# yard-ice-cpu.net
KiCad netlist of a schematic drawn in Altium Designer
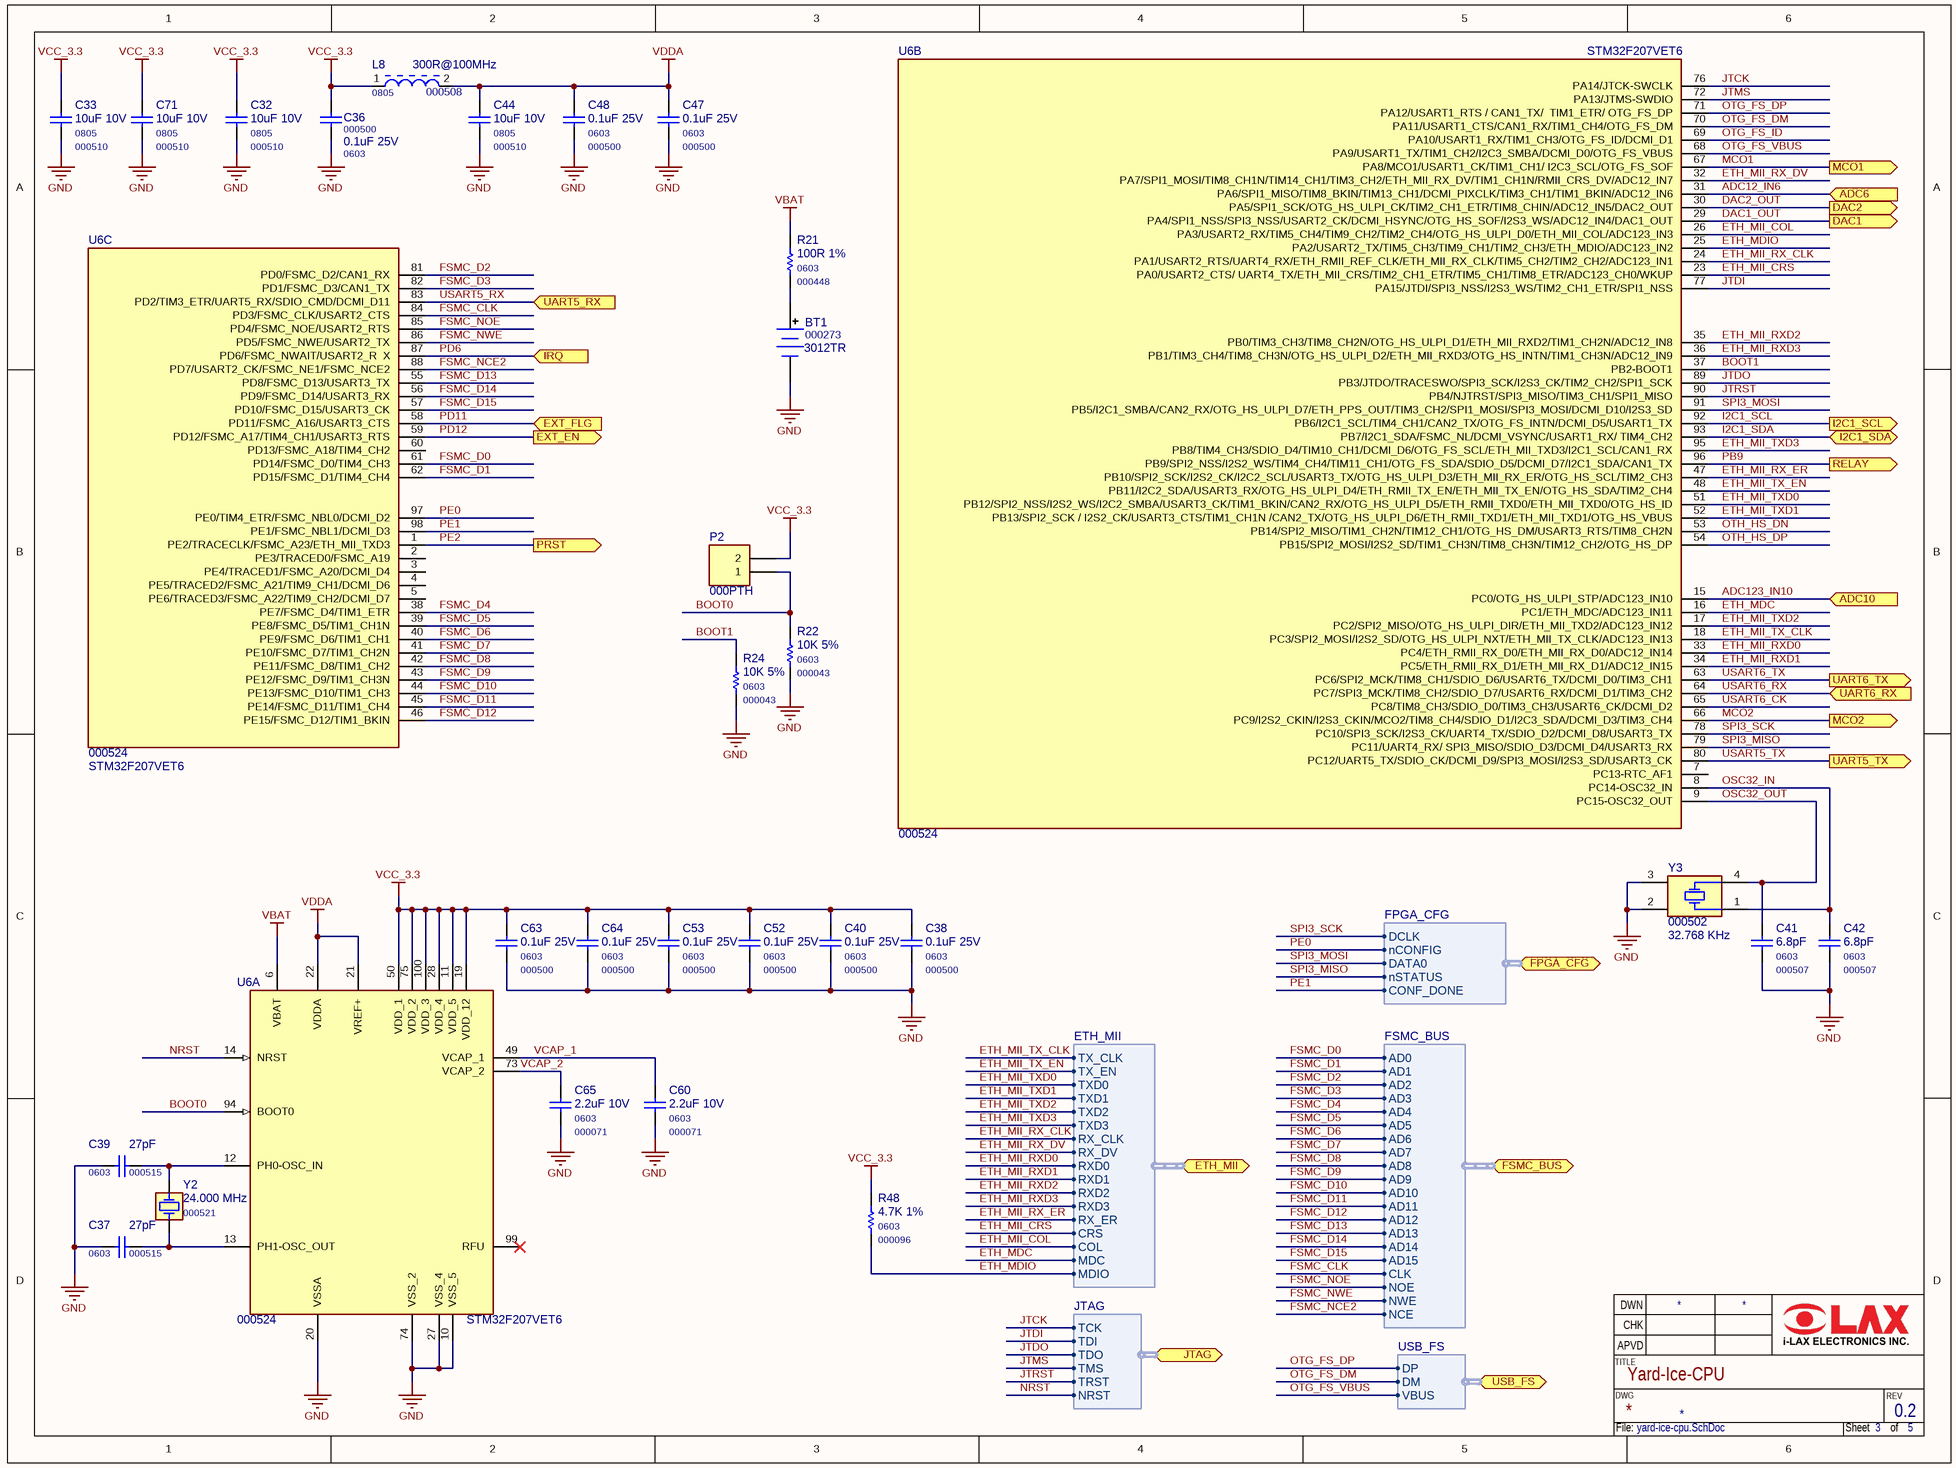
[diagram p0: yard-ice-cpu.SchDoc]

(export (version "E")
  (design (tool "Eeschema 10.0.6"))
  (components
    (comp (ref "BT1")
      (value "000273")
      (footprint "3012TR")
      (description "CR1620 SMD Battery Holder")
      (fields (field (name "MF") "Kestone") (field (name "ALTIUM_VALUE") "3012TR"))
      (libsource (lib "discrete-sm") (part "3012TR"))
    )
    (comp (ref "C32")
      (value "TDK")
      (footprint "C0805M")
      (description "SMD Ceramic Chip Capacitor - 0805 - X7R")
      (fields (field (name "ALTIUM_VALUE") "10uF 10V") (field (name "PACKAGE") "0805"))
      (libsource (lib "discrete-sm") (part "C0805"))
    )
    (comp (ref "C33")
      (value "TDK")
      (footprint "C0805M")
      (description "SMD Ceramic Chip Capacitor - 0805 - X7R")
      (fields (field (name "ALTIUM_VALUE") "10uF 10V") (field (name "PACKAGE") "0805"))
      (libsource (lib "discrete-sm") (part "C0805"))
    )
    (comp (ref "C36")
      (value "000500")
      (footprint "C0603M")
      (description "SMD Ceramic Chip Capacitor - 0603 - X7R")
      (fields
        (field (name "ALTIUM_VALUE") "0.1uF 25V")
        (field (name "PACKAGE") "0603")
        (field (name "MF") "TDK")
      )
      (libsource (lib "discrete-sm") (part "C0603"))
    )
    (comp (ref "C37")
      (value "000515")
      (footprint "C0603M")
      (description "SMD Ceramic Chip Capacitor - 0603")
      (fields (field (name "ALTIUM_VALUE") "27pF") (field (name "PACKAGE") "0603"))
      (libsource (lib "discrete-sm") (part "C0603"))
    )
    (comp (ref "C38")
      (value "000500")
      (footprint "C0603M")
      (description "SMD Ceramic Chip Capacitor - 0603 - X7R")
      (fields
        (field (name "ALTIUM_VALUE") "0.1uF 25V")
        (field (name "PACKAGE") "0603")
        (field (name "MF") "TDK")
      )
      (libsource (lib "discrete-sm") (part "C0603"))
    )
    (comp (ref "C39")
      (value "000515")
      (footprint "C0603M")
      (description "SMD Ceramic Chip Capacitor - 0603")
      (fields (field (name "ALTIUM_VALUE") "27pF") (field (name "PACKAGE") "0603"))
      (libsource (lib "discrete-sm") (part "C0603"))
    )
    (comp (ref "C40")
      (value "000500")
      (footprint "C0603M")
      (description "SMD Ceramic Chip Capacitor - 0603 - X7R")
      (fields
        (field (name "ALTIUM_VALUE") "0.1uF 25V")
        (field (name "PACKAGE") "0603")
        (field (name "MF") "TDK")
      )
      (libsource (lib "discrete-sm") (part "C0603"))
    )
    (comp (ref "C41")
      (value "000507")
      (footprint "C0603M")
      (description "SMD Ceramic Chip Capacitor - 0603")
      (fields (field (name "ALTIUM_VALUE") "6.8pF") (field (name "PACKAGE") "0603"))
      (libsource (lib "discrete-sm") (part "C0603"))
    )
    (comp (ref "C42")
      (value "000507")
      (footprint "C0603M")
      (description "SMD Ceramic Chip Capacitor - 0603")
      (fields (field (name "ALTIUM_VALUE") "6.8pF") (field (name "PACKAGE") "0603"))
      (libsource (lib "discrete-sm") (part "C0603"))
    )
    (comp (ref "C44")
      (value "000510")
      (footprint "C0805M")
      (description "SMD Ceramic Chip Capacitor - 0805 - X7R")
      (fields
        (field (name "ALTIUM_VALUE") "10uF 10V")
        (field (name "PACKAGE") "0805")
        (field (name "MF") "TDK")
      )
      (libsource (lib "discrete-sm") (part "C0805"))
    )
    (comp (ref "C47")
      (value "000500")
      (footprint "C0603M")
      (description "SMD Ceramic Chip Capacitor - 0603 - X7R")
      (fields
        (field (name "ALTIUM_VALUE") "0.1uF 25V")
        (field (name "PACKAGE") "0603")
        (field (name "MF") "TDK")
      )
      (libsource (lib "discrete-sm") (part "C0603"))
    )
    (comp (ref "C48")
      (value "000500")
      (footprint "C0603M")
      (description "SMD Ceramic Chip Capacitor - 0603 - X7R")
      (fields
        (field (name "ALTIUM_VALUE") "0.1uF 25V")
        (field (name "PACKAGE") "0603")
        (field (name "MF") "TDK")
      )
      (libsource (lib "discrete-sm") (part "C0603"))
    )
    (comp (ref "C52")
      (value "000500")
      (footprint "C0603M")
      (description "SMD Ceramic Chip Capacitor - 0603 - X7R")
      (fields
        (field (name "ALTIUM_VALUE") "0.1uF 25V")
        (field (name "PACKAGE") "0603")
        (field (name "MF") "TDK")
      )
      (libsource (lib "discrete-sm") (part "C0603"))
    )
    (comp (ref "C53")
      (value "000500")
      (footprint "C0603M")
      (description "SMD Ceramic Chip Capacitor - 0603 - X7R")
      (fields
        (field (name "ALTIUM_VALUE") "0.1uF 25V")
        (field (name "PACKAGE") "0603")
        (field (name "MF") "TDK")
      )
      (libsource (lib "discrete-sm") (part "C0603"))
    )
    (comp (ref "C60")
      (value "000071")
      (footprint "C0603M")
      (description "SMD Ceramic Chip Capacitor - 0603 - X7R")
      (fields
        (field (name "ALTIUM_VALUE") "2.2uF 10V")
        (field (name "PACKAGE") "0603")
        (field (name "MF") "Taiyo Yuden")
      )
      (libsource (lib "discrete-sm") (part "C0603"))
    )
    (comp (ref "C63")
      (value "000500")
      (footprint "C0603M")
      (description "SMD Ceramic Chip Capacitor - 0603 - X7R")
      (fields
        (field (name "ALTIUM_VALUE") "0.1uF 25V")
        (field (name "PACKAGE") "0603")
        (field (name "MF") "TDK")
      )
      (libsource (lib "discrete-sm") (part "C0603"))
    )
    (comp (ref "C64")
      (value "000500")
      (footprint "C0603M")
      (description "SMD Ceramic Chip Capacitor - 0603 - X7R")
      (fields
        (field (name "ALTIUM_VALUE") "0.1uF 25V")
        (field (name "PACKAGE") "0603")
        (field (name "MF") "TDK")
      )
      (libsource (lib "discrete-sm") (part "C0603"))
    )
    (comp (ref "C65")
      (value "000071")
      (footprint "C0603M")
      (description "SMD Ceramic Chip Capacitor - 0603 - X7R")
      (fields
        (field (name "ALTIUM_VALUE") "2.2uF 10V")
        (field (name "PACKAGE") "0603")
        (field (name "MF") "Taiyo Yuden")
      )
      (libsource (lib "discrete-sm") (part "C0603"))
    )
    (comp (ref "C71")
      (value "TDK")
      (footprint "C0805M")
      (description "SMD Ceramic Chip Capacitor - 0805 - X7R")
      (fields (field (name "ALTIUM_VALUE") "10uF 10V") (field (name "PACKAGE") "0805"))
      (libsource (lib "discrete-sm") (part "C0805"))
    )
    (comp (ref "L8")
      (value "000508")
      (footprint "L0805M")
      (description "SMD Ferrite Bead 0805")
      (fields
        (field (name "ALTIUM_VALUE") "300R@100MHz")
        (field (name "PACKAGE") "0805")
        (field (name "MF") "TDK")
      )
      (libsource (lib "discrete-sm") (part "L0805"))
    )
    (comp (ref "P2")
      (value "000PTH")
      (footprint "TSW-102-07-G-S")
      (description "Header, 2-Pin")
      (libsource (lib "samtec-board-to-board") (part "Header 2"))
    )
    (comp (ref "R21")
      (value "000448")
      (footprint "R0603M")
      (description "SMD Chip Resistor - 0603")
      (fields (field (name "ALTIUM_VALUE") "100R 1%") (field (name "PACKAGE") "0603"))
      (libsource (lib "discrete-sm") (part "R0603"))
    )
    (comp (ref "R22")
      (value "000043")
      (footprint "R0603M")
      (description "SMD Chip Resistor - 0603")
      (fields (field (name "ALTIUM_VALUE") "10K 5%") (field (name "PACKAGE") "0603"))
      (libsource (lib "discrete-sm") (part "R0603"))
    )
    (comp (ref "R24")
      (value "000043")
      (footprint "R0603M")
      (description "SMD Chip Resistor - 0603")
      (fields (field (name "ALTIUM_VALUE") "10K 5%") (field (name "PACKAGE") "0603"))
      (libsource (lib "discrete-sm") (part "R0603"))
    )
    (comp (ref "R48")
      (value "000096")
      (footprint "R0603M")
      (description "SMD Chip Resistor - 0603")
      (fields (field (name "ALTIUM_VALUE") "4.7K 1%") (field (name "PACKAGE") "0603"))
      (libsource (lib "discrete-sm") (part "R0603"))
    )
    (comp (ref "U6")
      (value "000524")
      (footprint "LQFP100")
      (description "ARM-Cortex M3 MCU, 512KB Flash/128+4KB RAM, USB, Eth")
      (fields (field (name "ALTIUM_VALUE") "STM32F207VET6") (field (name "MF") "ST"))
      (libsource (lib "st-mpu") (part "STM32F207VET6"))
    )
    (comp (ref "Y2")
      (value "000521")
      (footprint "ABM3-H")
      (description "Miniature Ceramic SMD Crystal")
      (fields (field (name "MF") "Abracon") (field (name "ALTIUM_VALUE") "24.000 MHz"))
      (libsource (lib "abracon") (part "ABM3"))
    )
    (comp (ref "Y3")
      (value "000502")
      (footprint "ABS25")
      (description "SMD Low Frequency Crystal")
      (fields (field (name "ALTIUM_VALUE") "32.768 KHz") (field (name "MF") "Abracon"))
      (libsource (lib "abracon") (part "ABS25"))
    )
  )
  (nets
    (net (code "6") (name "/ADC12_IN6") (class "Default")
      (node (ref "U6") (pin "31") (pinfunction "PA6/SPI1_MISO/TIM8_BKIN/TIM13_CH1/DCMI_PIXCLK/TIM3_CH1/TIM1_BKIN/ADC12_IN6_31") (pintype "tri_state"))
    )
    (net (code "7") (name "/ADC123_IN10") (class "Default")
      (node (ref "U6") (pin "15") (pinfunction "PC0/OTG_HS_ULPI_STP/ADC123_IN10_15") (pintype "tri_state"))
    )
    (net (code "8") (name "/BOOT0") (class "Default")
      (node (ref "P2") (pin "1") (pinfunction "1_1") (pintype "passive"))
      (node (ref "R22") (pin "2") (pinfunction "2_2") (pintype "passive"))
      (node (ref "U6") (pin "94") (pinfunction "BOOT0_94") (pintype "input"))
    )
    (net (code "9") (name "/BOOT1") (class "Default")
      (node (ref "R24") (pin "2") (pinfunction "2_2") (pintype "passive"))
      (node (ref "U6") (pin "37") (pinfunction "PB2-BOOT1_37") (pintype "tri_state"))
    )
    (net (code "10") (name "/DAC1_OUT") (class "Default")
      (node (ref "U6") (pin "29") (pinfunction "PA4/SPI1_NSS/SPI3_NSS/USART2_CK/DCMI_HSYNC/OTG_HS_SOF/I2S3_WS/ADC12_IN4/DAC1_OUT_29") (pintype "tri_state"))
    )
    (net (code "11") (name "/DAC2_OUT") (class "Default")
      (node (ref "U6") (pin "30") (pinfunction "PA5/SPI1_SCK/OTG_HS_ULPI_CK/TIM2_CH1_ETR/TIM8_CHIN/ADC12_IN5/DAC2_OUT_30") (pintype "tri_state"))
    )
    (net (code "12") (name "/ETH_MDC") (class "Default")
      (node (ref "U6") (pin "16") (pinfunction "PC1/ETH_MDC/ADC123_IN11_16") (pintype "tri_state"))
    )
    (net (code "13") (name "/ETH_MDIO") (class "Default")
      (node (ref "R48") (pin "1") (pinfunction "1_1") (pintype "passive"))
      (node (ref "U6") (pin "25") (pinfunction "PA2/USART2_TX/TIM5_CH3/TIM9_CH1/TIM2_CH3/ETH_MDIO/ADC123_IN2_25") (pintype "tri_state"))
    )
    (net (code "14") (name "/ETH_MII_COL") (class "Default")
      (node (ref "U6") (pin "26") (pinfunction "PA3/USART2_RX/TIM5_CH4/TIM9_CH2/TIM2_CH4/OTG_HS_ULPI_D0/ETH_MII_COL/ADC123_IN3_26") (pintype "tri_state"))
    )
    (net (code "15") (name "/ETH_MII_CRS") (class "Default")
      (node (ref "U6") (pin "23") (pinfunction "PA0/USART2_CTS/_UART4_TX/ETH_MII_CRS/TIM2_CH1_ETR/TIM5_CH1/TIM8_ETR/ADC123_CH0/WKUP_23") (pintype "tri_state"))
    )
    (net (code "16") (name "/ETH_MII_RXD0") (class "Default")
      (node (ref "U6") (pin "33") (pinfunction "PC4/ETH_RMII_RX_D0/ETH_MII_RX_D0/ADC12_IN14_33") (pintype "tri_state"))
    )
    (net (code "17") (name "/ETH_MII_RXD1") (class "Default")
      (node (ref "U6") (pin "34") (pinfunction "PC5/ETH_RMII_RX_D1/ETH_MII_RX_D1/ADC12_IN15_34") (pintype "tri_state"))
    )
    (net (code "18") (name "/ETH_MII_RXD2") (class "Default")
      (node (ref "U6") (pin "35") (pinfunction "PB0/TIM3_CH3/TIM8_CH2N/OTG_HS_ULPI_D1/ETH_MII_RXD2/TIM1_CH2N/ADC12_IN8_35") (pintype "tri_state"))
    )
    (net (code "19") (name "/ETH_MII_RXD3") (class "Default")
      (node (ref "U6") (pin "36") (pinfunction "PB1/TIM3_CH4/TIM8_CH3N/OTG_HS_ULPI_D2/ETH_MII_RXD3/OTG_HS_INTN/TIM1_CH3N/ADC12_IN9_36") (pintype "tri_state"))
    )
    (net (code "20") (name "/ETH_MII_RX_CLK") (class "Default")
      (node (ref "U6") (pin "24") (pinfunction "PA1/USART2_RTS/UART4_RX/ETH_RMII_REF_CLK/ETH_MII_RX_CLK/TIM5_CH2/TIM2_CH2/ADC123_IN1_24") (pintype "tri_state"))
    )
    (net (code "21") (name "/ETH_MII_RX_DV") (class "Default")
      (node (ref "U6") (pin "32") (pinfunction "PA7/SPI1_MOSI/TIM8_CH1N/TIM14_CH1/TIM3_CH2/ETH_MII_RX_DV/TIM1_CH1N/RMII_CRS_DV/ADC12_IN7_32") (pintype "tri_state"))
    )
    (net (code "22") (name "/ETH_MII_RX_ER") (class "Default")
      (node (ref "U6") (pin "47") (pinfunction "PB10/SPI2_SCK/I2S2_CK/I2C2_SCL/USART3_TX/OTG_HS_ULPI_D3/ETH_MII_RX_ER/OTG_HS_SCL/TIM2_CH3_47") (pintype "tri_state"))
    )
    (net (code "23") (name "/ETH_MII_TXD0") (class "Default")
      (node (ref "U6") (pin "51") (pinfunction "PB12/SPI2_NSS/I2S2_WS/I2C2_SMBA/USART3_CK/TIM1_BKIN/CAN2_RX/OTG_HS_ULPI_D5/ETH_RMII_TXD0/ETH_MII_TXD0/OTG_HS_ID_51") (pintype "tri_state"))
    )
    (net (code "24") (name "/ETH_MII_TXD1") (class "Default")
      (node (ref "U6") (pin "52") (pinfunction "PB13/SPI2_SCK_/_I2S2_CK/USART3_CTS/TIM1_CH1N_/CAN2_TX/OTG_HS_ULPI_D6/ETH_RMII_TXD1/ETH_MII_TXD1/OTG_HS_VBUS_52") (pintype "tri_state"))
    )
    (net (code "25") (name "/ETH_MII_TXD2") (class "Default")
      (node (ref "U6") (pin "17") (pinfunction "PC2/SPI2_MISO/OTG_HS_ULPI_DIR/ETH_MII_TXD2/ADC123_IN12_17") (pintype "tri_state"))
    )
    (net (code "26") (name "/ETH_MII_TXD3") (class "Default")
      (node (ref "U6") (pin "95") (pinfunction "PB8/TIM4_CH3/SDIO_D4/TIM10_CH1/DCMI_D6/OTG_FS_SCL/ETH_MII_TXD3/I2C1_SCL/CAN1_RX_95") (pintype "tri_state"))
    )
    (net (code "27") (name "/ETH_MII_TX_CLK") (class "Default")
      (node (ref "U6") (pin "18") (pinfunction "PC3/SPI2_MOSI/I2S2_SD/OTG_HS_ULPI_NXT/ETH_MII_TX_CLK/ADC123_IN13_18") (pintype "tri_state"))
    )
    (net (code "28") (name "/ETH_MII_TX_EN") (class "Default")
      (node (ref "U6") (pin "48") (pinfunction "PB11/I2C2_SDA/USART3_RX/OTG_HS_ULPI_D4/ETH_RMII_TX_EN/ETH_MII_TX_EN/OTG_HS_SDA/TIM2_CH4_48") (pintype "tri_state"))
    )
    (net (code "29") (name "/FSMC_CLK") (class "Default")
      (node (ref "U6") (pin "84") (pinfunction "PD3/FSMC_CLK/USART2_CTS_84") (pintype "tri_state"))
    )
    (net (code "30") (name "/FSMC_D0") (class "Default")
      (node (ref "U6") (pin "61") (pinfunction "PD14/FSMC_D0/TIM4_CH3_61") (pintype "tri_state"))
    )
    (net (code "31") (name "/FSMC_D1") (class "Default")
      (node (ref "U6") (pin "62") (pinfunction "PD15/FSMC_D1/TIM4_CH4_62") (pintype "tri_state"))
    )
    (net (code "32") (name "/FSMC_D2") (class "Default")
      (node (ref "U6") (pin "81") (pinfunction "PD0/FSMC_D2/CAN1_RX_81") (pintype "tri_state"))
    )
    (net (code "33") (name "/FSMC_D3") (class "Default")
      (node (ref "U6") (pin "82") (pinfunction "PD1/FSMC_D3/CAN1_TX_82") (pintype "tri_state"))
    )
    (net (code "34") (name "/FSMC_D4") (class "Default")
      (node (ref "U6") (pin "38") (pinfunction "PE7/FSMC_D4/TIM1_ETR_38") (pintype "tri_state"))
    )
    (net (code "35") (name "/FSMC_D5") (class "Default")
      (node (ref "U6") (pin "39") (pinfunction "PE8/FSMC_D5/TIM1_CH1N_39") (pintype "tri_state"))
    )
    (net (code "36") (name "/FSMC_D6") (class "Default")
      (node (ref "U6") (pin "40") (pinfunction "PE9/FSMC_D6/TIM1_CH1_40") (pintype "tri_state"))
    )
    (net (code "37") (name "/FSMC_D7") (class "Default")
      (node (ref "U6") (pin "41") (pinfunction "PE10/FSMC_D7/TIM1_CH2N_41") (pintype "tri_state"))
    )
    (net (code "38") (name "/FSMC_D8") (class "Default")
      (node (ref "U6") (pin "42") (pinfunction "PE11/FSMC_D8/TIM1_CH2_42") (pintype "tri_state"))
    )
    (net (code "39") (name "/FSMC_D9") (class "Default")
      (node (ref "U6") (pin "43") (pinfunction "PE12/FSMC_D9/TIM1_CH3N_43") (pintype "tri_state"))
    )
    (net (code "40") (name "/FSMC_D10") (class "Default")
      (node (ref "U6") (pin "44") (pinfunction "PE13/FSMC_D10/TIM1_CH3_44") (pintype "tri_state"))
    )
    (net (code "41") (name "/FSMC_D11") (class "Default")
      (node (ref "U6") (pin "45") (pinfunction "PE14/FSMC_D11/TIM1_CH4_45") (pintype "tri_state"))
    )
    (net (code "42") (name "/FSMC_D12") (class "Default")
      (node (ref "U6") (pin "46") (pinfunction "PE15/FSMC_D12/TIM1_BKIN_46") (pintype "tri_state"))
    )
    (net (code "43") (name "/FSMC_D13") (class "Default")
      (node (ref "U6") (pin "55") (pinfunction "PD8/FSMC_D13/USART3_TX_55") (pintype "tri_state"))
    )
    (net (code "44") (name "/FSMC_D14") (class "Default")
      (node (ref "U6") (pin "56") (pinfunction "PD9/FSMC_D14/USART3_RX_56") (pintype "tri_state"))
    )
    (net (code "45") (name "/FSMC_D15") (class "Default")
      (node (ref "U6") (pin "57") (pinfunction "PD10/FSMC_D15/USART3_CK_57") (pintype "tri_state"))
    )
    (net (code "46") (name "/FSMC_NCE2") (class "Default")
      (node (ref "U6") (pin "88") (pinfunction "PD7/USART2_CK/FSMC_NE1/FSMC_NCE2_88") (pintype "tri_state"))
    )
    (net (code "47") (name "/FSMC_NOE") (class "Default")
      (node (ref "U6") (pin "85") (pinfunction "PD4/FSMC_NOE/USART2_RTS_85") (pintype "tri_state"))
    )
    (net (code "48") (name "/FSMC_NWE") (class "Default")
      (node (ref "U6") (pin "86") (pinfunction "PD5/FSMC_NWE/USART2_TX_86") (pintype "tri_state"))
    )
    (net (code "49") (name "/I2C1_SCL") (class "Default")
      (node (ref "U6") (pin "92") (pinfunction "PB6/I2C1_SCL/TIM4_CH1/CAN2_TX/OTG_FS_INTN/DCMI_D5/USART1_TX_92") (pintype "tri_state"))
    )
    (net (code "50") (name "/I2C1_SDA") (class "Default")
      (node (ref "U6") (pin "93") (pinfunction "PB7/I2C1_SDA/FSMC_NL/DCMI_VSYNC/USART1_RX/_TIM4_CH2_93") (pintype "tri_state"))
    )
    (net (code "51") (name "/JTCK") (class "Default")
      (node (ref "U6") (pin "76") (pinfunction "PA14/JTCK-SWCLK_76") (pintype "tri_state"))
    )
    (net (code "52") (name "/JTDI") (class "Default")
      (node (ref "U6") (pin "77") (pinfunction "PA15/JTDI/SPI3_NSS/I2S3_WS/TIM2_CH1_ETR/SPI1_NSS_77") (pintype "tri_state"))
    )
    (net (code "53") (name "/JTDO") (class "Default")
      (node (ref "U6") (pin "89") (pinfunction "PB3/JTDO/TRACESWO/SPI3_SCK/I2S3_CK/TIM2_CH2/SPI1_SCK_89") (pintype "tri_state"))
    )
    (net (code "54") (name "/JTMS") (class "Default")
      (node (ref "U6") (pin "72") (pinfunction "PA13/JTMS-SWDIO_72") (pintype "tri_state"))
    )
    (net (code "55") (name "/JTRST") (class "Default")
      (node (ref "U6") (pin "90") (pinfunction "PB4/NJTRST/SPI3_MISO/TIM3_CH1/SPI1_MISO_90") (pintype "tri_state"))
    )
    (net (code "56") (name "/MCO1") (class "Default")
      (node (ref "U6") (pin "67") (pinfunction "PA8/MCO1/USART1_CK/TIM1_CH1/_I2C3_SCL/OTG_FS_SOF_67") (pintype "tri_state"))
    )
    (net (code "57") (name "/MCO2") (class "Default")
      (node (ref "U6") (pin "66") (pinfunction "PC9/I2S2_CKIN/I2S3_CKIN/MCO2/TIM8_CH4/SDIO_D1/I2C3_SDA/DCMI_D3/TIM3_CH4_66") (pintype "tri_state"))
    )
    (net (code "58") (name "/NRST") (class "Default")
      (node (ref "U6") (pin "14") (pinfunction "NRST_14") (pintype "input"))
    )
    (net (code "59") (name "/OSC32_IN") (class "Default")
      (node (ref "C42") (pin "2") (pinfunction "2_2") (pintype "passive"))
      (node (ref "U6") (pin "8") (pinfunction "PC14-OSC32_IN_8") (pintype "tri_state"))
      (node (ref "Y3") (pin "1") (pinfunction "1_1") (pintype "passive"))
    )
    (net (code "60") (name "/OSC32_OUT") (class "Default")
      (node (ref "C41") (pin "2") (pinfunction "2_2") (pintype "passive"))
      (node (ref "U6") (pin "9") (pinfunction "PC15-OSC32_OUT_9") (pintype "tri_state"))
      (node (ref "Y3") (pin "4") (pinfunction "4_4") (pintype "passive"))
    )
    (net (code "61") (name "/OTG_FS_DM") (class "Default")
      (node (ref "U6") (pin "70") (pinfunction "PA11/USART1_CTS/CAN1_RX/TIM1_CH4/OTG_FS_DM_70") (pintype "tri_state"))
    )
    (net (code "62") (name "/OTG_FS_DP") (class "Default")
      (node (ref "U6") (pin "71") (pinfunction "PA12/USART1_RTS_/_CAN1_TX/__TIM1_ETR/_OTG_FS_DP_71") (pintype "tri_state"))
    )
    (net (code "63") (name "/OTG_FS_ID") (class "Default")
      (node (ref "U6") (pin "69") (pinfunction "PA10/USART1_RX/TIM1_CH3/OTG_FS_ID/DCMI_D1_69") (pintype "tri_state"))
    )
    (net (code "64") (name "/OTG_FS_VBUS") (class "Default")
      (node (ref "U6") (pin "68") (pinfunction "PA9/USART1_TX/TIM1_CH2/I2C3_SMBA/DCMI_D0/OTG_FS_VBUS_68") (pintype "tri_state"))
    )
    (net (code "65") (name "/OTH_HS_DN") (class "Default")
      (node (ref "U6") (pin "53") (pinfunction "PB14/SPI2_MISO/TIM1_CH2N/TIM12_CH1/OTG_HS_DM/USART3_RTS/TIM8_CH2N_53") (pintype "tri_state"))
    )
    (net (code "66") (name "/OTH_HS_DP") (class "Default")
      (node (ref "U6") (pin "54") (pinfunction "PB15/SPI2_MOSI/I2S2_SD/TIM1_CH3N/TIM8_CH3N/TIM12_CH2/OTG_HS_DP_54") (pintype "tri_state"))
    )
    (net (code "67") (name "/PB9") (class "Default")
      (node (ref "U6") (pin "96") (pinfunction "PB9/SPI2_NSS/I2S2_WS/TIM4_CH4/TIM11_CH1/OTG_FS_SDA/SDIO_D5/DCMI_D7/I2C1_SDA/CAN1_TX_96") (pintype "tri_state"))
    )
    (net (code "68") (name "/PD6") (class "Default")
      (node (ref "U6") (pin "87") (pinfunction "PD6/FSMC_NWAIT/USART2_R__X_87") (pintype "tri_state"))
    )
    (net (code "69") (name "/PD11") (class "Default")
      (node (ref "U6") (pin "58") (pinfunction "PD11/FSMC_A16/USART3_CTS_58") (pintype "tri_state"))
    )
    (net (code "70") (name "/PD12") (class "Default")
      (node (ref "U6") (pin "59") (pinfunction "PD12/FSMC_A17/TIM4_CH1/USART3_RTS_59") (pintype "tri_state"))
    )
    (net (code "71") (name "/PE0") (class "Default")
      (node (ref "U6") (pin "97") (pinfunction "PE0/TIM4_ETR/FSMC_NBL0/DCMI_D2_97") (pintype "tri_state"))
    )
    (net (code "72") (name "/PE1") (class "Default")
      (node (ref "U6") (pin "98") (pinfunction "PE1/FSMC_NBL1/DCMI_D3_98") (pintype "tri_state"))
    )
    (net (code "73") (name "/PE2") (class "Default")
      (node (ref "U6") (pin "1") (pinfunction "PE2/TRACECLK/FSMC_A23/ETH_MII_TXD3_1") (pintype "tri_state"))
    )
    (net (code "74") (name "/SPI3_MISO") (class "Default")
      (node (ref "U6") (pin "79") (pinfunction "PC11/UART4_RX/_SPI3_MISO/SDIO_D3/DCMI_D4/USART3_RX_79") (pintype "tri_state"))
    )
    (net (code "75") (name "/SPI3_MOSI") (class "Default")
      (node (ref "U6") (pin "91") (pinfunction "PB5/I2C1_SMBA/CAN2_RX/OTG_HS_ULPI_D7/ETH_PPS_OUT/TIM3_CH2/SPI1_MOSI/SPI3_MOSI/DCMI_D10/I2S3_SD_91") (pintype "tri_state"))
    )
    (net (code "76") (name "/SPI3_SCK") (class "Default")
      (node (ref "U6") (pin "78") (pinfunction "PC10/SPI3_SCK/I2S3_CK/UART4_TX/SDIO_D2/DCMI_D8/USART3_TX_78") (pintype "tri_state"))
    )
    (net (code "77") (name "/USART5_RX") (class "Default")
      (node (ref "U6") (pin "83") (pinfunction "PD2/TIM3_ETR/UART5_RX/SDIO_CMD/DCMI_D11_83") (pintype "tri_state"))
    )
    (net (code "78") (name "/USART5_TX") (class "Default")
      (node (ref "U6") (pin "80") (pinfunction "PC12/UART5_TX/SDIO_CK/DCMI_D9/SPI3_MOSI/I2S3_SD/USART3_CK_80") (pintype "tri_state"))
    )
    (net (code "79") (name "/USART6_CK") (class "Default")
      (node (ref "U6") (pin "65") (pinfunction "PC8/TIM8_CH3/SDIO_D0/TIM3_CH3/USART6_CK/DCMI_D2_65") (pintype "tri_state"))
    )
    (net (code "80") (name "/USART6_RX") (class "Default")
      (node (ref "U6") (pin "64") (pinfunction "PC7/SPI3_MCK/TIM8_CH2/SDIO_D7/USART6_RX/DCMI_D1/TIM3_CH2_64") (pintype "tri_state"))
    )
    (net (code "81") (name "/USART6_TX") (class "Default")
      (node (ref "U6") (pin "63") (pinfunction "PC6/SPI2_MCK/TIM8_CH1/SDIO_D6/USART6_TX/DCMI_D0/TIM3_CH1_63") (pintype "tri_state"))
    )
    (net (code "82") (name "/VCAP_1") (class "Default")
      (node (ref "C60") (pin "1") (pinfunction "1_1") (pintype "passive"))
      (node (ref "U6") (pin "49") (pinfunction "VCAP_1_49") (pintype "power_in"))
    )
    (net (code "83") (name "/VCAP_2") (class "Default")
      (node (ref "C65") (pin "1") (pinfunction "1_1") (pintype "passive"))
      (node (ref "U6") (pin "73") (pinfunction "VCAP_2_73") (pintype "power_in"))
    )
    (net (code "89") (name "GND") (class "Default")
      (node (ref "BT1") (pin "2") (pinfunction "-_2") (pintype "passive"))
      (node (ref "C32") (pin "2") (pinfunction "2_2") (pintype "passive"))
      (node (ref "C33") (pin "2") (pinfunction "2_2") (pintype "passive"))
      (node (ref "C36") (pin "2") (pinfunction "2_2") (pintype "passive"))
      (node (ref "C37") (pin "1") (pinfunction "1_1") (pintype "passive"))
      (node (ref "C38") (pin "2") (pinfunction "2_2") (pintype "passive"))
      (node (ref "C39") (pin "1") (pinfunction "1_1") (pintype "passive"))
      (node (ref "C40") (pin "2") (pinfunction "2_2") (pintype "passive"))
      (node (ref "C41") (pin "1") (pinfunction "1_1") (pintype "passive"))
      (node (ref "C42") (pin "1") (pinfunction "1_1") (pintype "passive"))
      (node (ref "C44") (pin "2") (pinfunction "2_2") (pintype "passive"))
      (node (ref "C47") (pin "2") (pinfunction "2_2") (pintype "passive"))
      (node (ref "C48") (pin "2") (pinfunction "2_2") (pintype "passive"))
      (node (ref "C52") (pin "2") (pinfunction "2_2") (pintype "passive"))
      (node (ref "C53") (pin "2") (pinfunction "2_2") (pintype "passive"))
      (node (ref "C60") (pin "2") (pinfunction "2_2") (pintype "passive"))
      (node (ref "C63") (pin "2") (pinfunction "2_2") (pintype "passive"))
      (node (ref "C64") (pin "2") (pinfunction "2_2") (pintype "passive"))
      (node (ref "C65") (pin "2") (pinfunction "2_2") (pintype "passive"))
      (node (ref "C71") (pin "2") (pinfunction "2_2") (pintype "passive"))
      (node (ref "R22") (pin "1") (pinfunction "1_1") (pintype "passive"))
      (node (ref "R24") (pin "1") (pinfunction "1_1") (pintype "passive"))
      (node (ref "U6") (pin "10") (pinfunction "VSS_5_10") (pintype "power_in"))
      (node (ref "U6") (pin "20") (pinfunction "VSSA_20") (pintype "power_in"))
      (node (ref "U6") (pin "27") (pinfunction "VSS_4_27") (pintype "power_in"))
      (node (ref "U6") (pin "74") (pinfunction "VSS_2_74") (pintype "power_in"))
      (node (ref "Y3") (pin "2") (pinfunction "2_2") (pintype "passive"))
      (node (ref "Y3") (pin "3") (pinfunction "3_3") (pintype "passive"))
    )
    (net (code "90") (name "Net-(BT1-+)") (class "Default")
      (node (ref "BT1") (pin "1") (pinfunction "+_1") (pintype "passive"))
      (node (ref "R21") (pin "1") (pinfunction "1_1") (pintype "passive"))
    )
    (net (code "91") (name "Net-(U6A-PH0-OSC_IN)") (class "Default")
      (node (ref "C39") (pin "2") (pinfunction "2_2") (pintype "passive"))
      (node (ref "U6") (pin "12") (pinfunction "PH0-OSC_IN_12") (pintype "tri_state"))
      (node (ref "Y2") (pin "1") (pinfunction "1_1") (pintype "passive"))
    )
    (net (code "92") (name "Net-(U6A-PH1-OSC_OUT)") (class "Default")
      (node (ref "C37") (pin "2") (pinfunction "2_2") (pintype "passive"))
      (node (ref "U6") (pin "13") (pinfunction "PH1-OSC_OUT_13") (pintype "tri_state"))
      (node (ref "Y2") (pin "2") (pinfunction "2_2") (pintype "passive"))
    )
    (net (code "93") (name "VBAT") (class "Default")
      (node (ref "R21") (pin "2") (pinfunction "2_2") (pintype "passive"))
      (node (ref "U6") (pin "6") (pinfunction "VBAT_6") (pintype "power_in"))
    )
    (net (code "94") (name "VCC_3.3") (class "Default")
      (node (ref "C32") (pin "1") (pinfunction "1_1") (pintype "passive"))
      (node (ref "C33") (pin "1") (pinfunction "1_1") (pintype "passive"))
      (node (ref "C36") (pin "1") (pinfunction "1_1") (pintype "passive"))
      (node (ref "C38") (pin "1") (pinfunction "1_1") (pintype "passive"))
      (node (ref "C40") (pin "1") (pinfunction "1_1") (pintype "passive"))
      (node (ref "C52") (pin "1") (pinfunction "1_1") (pintype "passive"))
      (node (ref "C53") (pin "1") (pinfunction "1_1") (pintype "passive"))
      (node (ref "C63") (pin "1") (pinfunction "1_1") (pintype "passive"))
      (node (ref "C64") (pin "1") (pinfunction "1_1") (pintype "passive"))
      (node (ref "C71") (pin "1") (pinfunction "1_1") (pintype "passive"))
      (node (ref "L8") (pin "1") (pinfunction "1_1") (pintype "passive"))
      (node (ref "P2") (pin "2") (pinfunction "2_2") (pintype "passive"))
      (node (ref "R48") (pin "2") (pinfunction "2_2") (pintype "passive"))
      (node (ref "U6") (pin "100") (pinfunction "VDD_3_100") (pintype "power_in"))
      (node (ref "U6") (pin "11") (pinfunction "VDD_5_11") (pintype "power_in"))
      (node (ref "U6") (pin "19") (pinfunction "VDD_12_19") (pintype "power_in"))
      (node (ref "U6") (pin "28") (pinfunction "VDD_4_28") (pintype "power_in"))
      (node (ref "U6") (pin "50") (pinfunction "VDD_1_50") (pintype "power_in"))
      (node (ref "U6") (pin "75") (pinfunction "VDD_2_75") (pintype "power_in"))
    )
    (net (code "95") (name "VDDA") (class "Default")
      (node (ref "C44") (pin "1") (pinfunction "1_1") (pintype "passive"))
      (node (ref "C47") (pin "1") (pinfunction "1_1") (pintype "passive"))
      (node (ref "C48") (pin "1") (pinfunction "1_1") (pintype "passive"))
      (node (ref "L8") (pin "2") (pinfunction "2_2") (pintype "passive"))
      (node (ref "U6") (pin "21") (pinfunction "VREF+_21") (pintype "power_in"))
      (node (ref "U6") (pin "22") (pinfunction "VDDA_22") (pintype "power_in"))
    )
    (net (code "96") (name "unconnected-(U6A-RFU-Pad99)") (class "Default")
      (node (ref "U6") (pin "99") (pinfunction "RFU_99") (pintype "passive+no_connect"))
    )
    (net (code "97") (name "unconnected-(U6B-PC13-RTC_AF1-Pad7)") (class "Default")
      (node (ref "U6") (pin "7") (pinfunction "PC13-RTC_AF1_7") (pintype "tri_state"))
    )
    (net (code "98") (name "unconnected-(U6C-PD13{slash}FSMC_A18{slash}TIM4_CH2-Pad60)") (class "Default")
      (node (ref "U6") (pin "60") (pinfunction "PD13/FSMC_A18/TIM4_CH2_60") (pintype "tri_state"))
    )
    (net (code "99") (name "unconnected-(U6C-PE3{slash}TRACED0{slash}FSMC_A19-Pad2)") (class "Default")
      (node (ref "U6") (pin "2") (pinfunction "PE3/TRACED0/FSMC_A19_2") (pintype "tri_state"))
    )
    (net (code "100") (name "unconnected-(U6C-PE4{slash}TRACED1{slash}FSMC_A20{slash}DCMI_D4-Pad3)") (class "Default")
      (node (ref "U6") (pin "3") (pinfunction "PE4/TRACED1/FSMC_A20/DCMI_D4_3") (pintype "tri_state"))
    )
    (net (code "101") (name "unconnected-(U6C-PE5{slash}TRACED2{slash}FSMC_A21{slash}TIM9_CH1{slash}DCMI_D6-Pad4)") (class "Default")
      (node (ref "U6") (pin "4") (pinfunction "PE5/TRACED2/FSMC_A21/TIM9_CH1/DCMI_D6_4") (pintype "tri_state"))
    )
    (net (code "102") (name "unconnected-(U6C-PE6{slash}TRACED3{slash}FSMC_A22{slash}TIM9_CH2{slash}DCMI_D7-Pad5)") (class "Default")
      (node (ref "U6") (pin "5") (pinfunction "PE6/TRACED3/FSMC_A22/TIM9_CH2/DCMI_D7_5") (pintype "tri_state"))
    )
  )
)
